# ziffy_board_v2.net
KiCad netlist of a schematic drawn in EAGLE
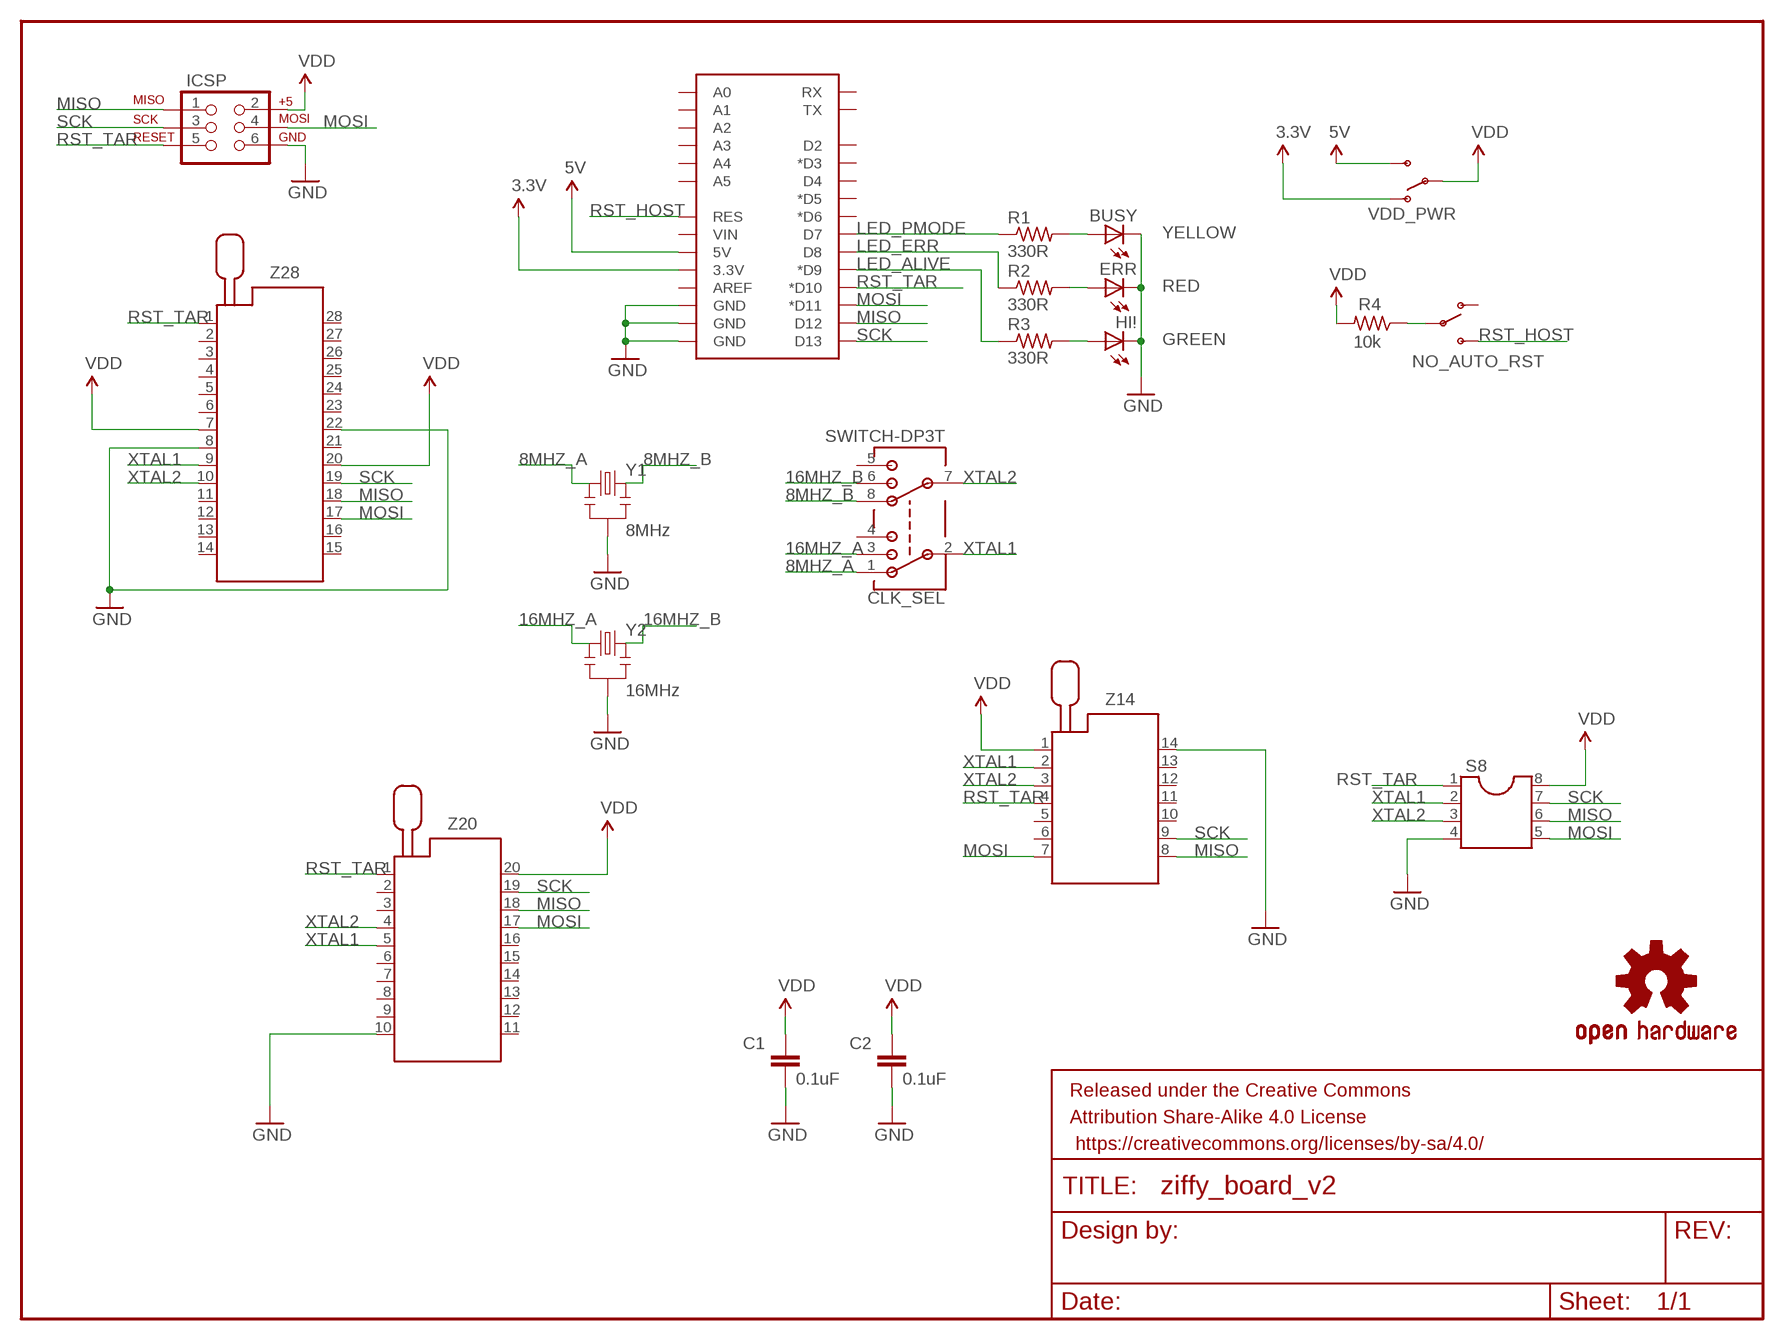
[diagram p0: schematic, sheet 1]

(export (version "E")
  (design (tool "Eeschema 10.0.6"))
  (components
    (comp (ref "BUSY")
      (value "YELLOW")
      (footprint "eagle-import:LED3MM")
      (libsource (lib "eagle-import") (part "LED3MM"))
    )
    (comp (ref "C1")
      (value "0.1uF")
      (footprint "eagle-import:C025-025X050")
      (libsource (lib "eagle-import") (part "C-EU025-025X050"))
    )
    (comp (ref "C2")
      (value "0.1uF")
      (footprint "eagle-import:C025-025X050")
      (libsource (lib "eagle-import") (part "C-EU025-025X050"))
    )
    (comp (ref "CLK_SEL")
      (value "SWITCH-DP3T")
      (footprint "eagle-import:SWITCH-DP3T")
      (libsource (lib "eagle-import") (part "SWITCH-DP3T"))
    )
    (comp (ref "ERR")
      (value "RED")
      (footprint "eagle-import:LED3MM")
      (libsource (lib "eagle-import") (part "LED3MM"))
    )
    (comp (ref "FRAME1")
      (value "FRAME-LETTER")
      (footprint "eagle-import:CREATIVE_COMMONS")
      (libsource (lib "eagle-import") (part "FRAME-LETTER"))
    )
    (comp (ref "HI!")
      (value "GREEN")
      (footprint "eagle-import:LED3MM")
      (libsource (lib "eagle-import") (part "LED3MM"))
    )
    (comp (ref "ICSP")
      (value "AVR_SPI_PRG_6PTH")
      (footprint "eagle-import:2X3")
      (libsource (lib "eagle-import") (part "AVR_SPI_PRG_6PTH"))
    )
    (comp (ref "LOGO1")
      (value "OSHW-LOGOS")
      (footprint "eagle-import:OSHW-LOGO-S")
      (libsource (lib "eagle-import") (part "OSHW-LOGOS"))
    )
    (comp (ref "NO_AUTO_RST")
      (value "SWITCH-SPDTPTH")
      (footprint "eagle-import:SWITCH-SPDT")
      (libsource (lib "eagle-import") (part "SWITCH-SPDTPTH"))
    )
    (comp (ref "R1")
      (value "330R")
      (footprint "eagle-import:0204_5")
      (libsource (lib "eagle-import") (part "R-US_0204/5"))
    )
    (comp (ref "R2")
      (value "330R")
      (footprint "eagle-import:0204_5")
      (libsource (lib "eagle-import") (part "R-US_0204/5"))
    )
    (comp (ref "R3")
      (value "330R")
      (footprint "eagle-import:0204_5")
      (libsource (lib "eagle-import") (part "R-US_0204/5"))
    )
    (comp (ref "R4")
      (value "10k")
      (footprint "eagle-import:0204_5")
      (libsource (lib "eagle-import") (part "R-US_0204/5"))
    )
    (comp (ref "S8")
      (value "DIPSHIT")
      (footprint "eagle-import:DIL08")
      (libsource (lib "eagle-import") (part "DIL8"))
    )
    (comp (ref "U$1")
      (value "ARDUINO_SHIELD")
      (footprint "eagle-import:SHIELD_NO_OUTLINE")
      (libsource (lib "eagle-import") (part "ARDUINO_SHIELD"))
    )
    (comp (ref "VDD_PWR")
      (value "SWITCH-SPDTPTH")
      (footprint "eagle-import:SWITCH-SPDT")
      (libsource (lib "eagle-import") (part "SWITCH-SPDTPTH"))
    )
    (comp (ref "Y1")
      (value "8MHz")
      (footprint "eagle-import:RESONATOR-PTH")
      (libsource (lib "eagle-import") (part "RESONATORPTH"))
    )
    (comp (ref "Y2")
      (value "16MHz")
      (footprint "eagle-import:RESONATOR-PTH")
      (libsource (lib "eagle-import") (part "RESONATORPTH"))
    )
    (comp (ref "Z14")
      (value "ZIF14")
      (footprint "eagle-import:ZIF14")
      (fields (field (name "MF") "3M") (field (name "MPN") "214-3339-00-0602J"))
      (libsource (lib "eagle-import") (part "ZIF14"))
    )
    (comp (ref "Z20")
      (value "ZIF20")
      (footprint "eagle-import:ZIF20")
      (fields (field (name "MF") "3M") (field (name "MPN") "220-3342-00-0602J"))
      (libsource (lib "eagle-import") (part "ZIF20"))
    )
    (comp (ref "Z28")
      (value "ZIF28")
      (footprint "eagle-import:ZIF28")
      (libsource (lib "eagle-import") (part "ZIF28"))
    )
  )
  (nets
    (net (code "1") (name "/8MHZ_A") (class "Default")
      (node (ref "CLK_SEL") (pin "1") (pinfunction "1_1") (pintype "bidirectional"))
      (node (ref "Y1") (pin "1") (pinfunction "1_1") (pintype "passive"))
    )
    (net (code "2") (name "/8MHZ_B") (class "Default")
      (node (ref "CLK_SEL") (pin "8") (pinfunction "8_8") (pintype "bidirectional"))
      (node (ref "Y1") (pin "3") (pinfunction "3_3") (pintype "passive"))
    )
    (net (code "3") (name "/16MHZ_A") (class "Default")
      (node (ref "CLK_SEL") (pin "3") (pinfunction "3_3") (pintype "bidirectional"))
      (node (ref "Y2") (pin "1") (pinfunction "1_1") (pintype "passive"))
    )
    (net (code "4") (name "/16MHZ_B") (class "Default")
      (node (ref "CLK_SEL") (pin "6") (pinfunction "6_6") (pintype "bidirectional"))
      (node (ref "Y2") (pin "3") (pinfunction "3_3") (pintype "passive"))
    )
    (net (code "5") (name "/LED_ALIVE") (class "Default")
      (node (ref "R3") (pin "1") (pinfunction "1_1") (pintype "passive"))
      (node (ref "U$1") (pin "D9") (pinfunction "*D9_D9") (pintype "bidirectional"))
    )
    (net (code "6") (name "/LED_ERR") (class "Default")
      (node (ref "R2") (pin "1") (pinfunction "1_1") (pintype "passive"))
      (node (ref "U$1") (pin "D8") (pinfunction "D8_D8") (pintype "bidirectional"))
    )
    (net (code "7") (name "/LED_PMODE") (class "Default")
      (node (ref "R1") (pin "1") (pinfunction "1_1") (pintype "passive"))
      (node (ref "U$1") (pin "D7") (pinfunction "D7_D7") (pintype "bidirectional"))
    )
    (net (code "8") (name "/MISO") (class "Default")
      (node (ref "ICSP") (pin "1") (pinfunction "1_1") (pintype "passive"))
      (node (ref "S8") (pin "6") (pinfunction "6_6") (pintype "passive"))
      (node (ref "U$1") (pin "D12") (pinfunction "D12_D12") (pintype "bidirectional"))
      (node (ref "Z14") (pin "8") (pinfunction "8_8") (pintype "passive"))
      (node (ref "Z20") (pin "18") (pinfunction "18_18") (pintype "passive"))
      (node (ref "Z28") (pin "18") (pinfunction "18_18") (pintype "passive"))
    )
    (net (code "9") (name "/MOSI") (class "Default")
      (node (ref "ICSP") (pin "4") (pinfunction "4_4") (pintype "passive"))
      (node (ref "S8") (pin "5") (pinfunction "5_5") (pintype "passive"))
      (node (ref "U$1") (pin "D11") (pinfunction "*D11_D11") (pintype "bidirectional"))
      (node (ref "Z14") (pin "7") (pinfunction "7_7") (pintype "passive"))
      (node (ref "Z20") (pin "17") (pinfunction "17_17") (pintype "passive"))
      (node (ref "Z28") (pin "17") (pinfunction "17_17") (pintype "passive"))
    )
    (net (code "10") (name "/RST_HOST") (class "Default")
      (node (ref "NO_AUTO_RST") (pin "3") (pinfunction "S_3") (pintype "passive"))
      (node (ref "U$1") (pin "RES") (pinfunction "RES_RES") (pintype "bidirectional"))
    )
    (net (code "11") (name "/RST_TAR") (class "Default")
      (node (ref "ICSP") (pin "5") (pinfunction "5_5") (pintype "passive"))
      (node (ref "S8") (pin "1") (pinfunction "1_1") (pintype "passive"))
      (node (ref "U$1") (pin "D10") (pinfunction "*D10_D10") (pintype "bidirectional"))
      (node (ref "Z14") (pin "4") (pinfunction "4_4") (pintype "passive"))
      (node (ref "Z20") (pin "1") (pinfunction "1_1") (pintype "passive"))
      (node (ref "Z28") (pin "1") (pinfunction "1_1") (pintype "passive"))
    )
    (net (code "12") (name "/SCK") (class "Default")
      (node (ref "ICSP") (pin "3") (pinfunction "3_3") (pintype "passive"))
      (node (ref "S8") (pin "7") (pinfunction "7_7") (pintype "passive"))
      (node (ref "U$1") (pin "D13") (pinfunction "D13_D13") (pintype "bidirectional"))
      (node (ref "Z14") (pin "9") (pinfunction "9_9") (pintype "passive"))
      (node (ref "Z20") (pin "19") (pinfunction "19_19") (pintype "passive"))
      (node (ref "Z28") (pin "19") (pinfunction "19_19") (pintype "passive"))
    )
    (net (code "13") (name "/XTAL1") (class "Default")
      (node (ref "CLK_SEL") (pin "2") (pinfunction "2_2") (pintype "bidirectional"))
      (node (ref "S8") (pin "2") (pinfunction "2_2") (pintype "passive"))
      (node (ref "Z14") (pin "2") (pinfunction "2_2") (pintype "passive"))
      (node (ref "Z20") (pin "5") (pinfunction "5_5") (pintype "passive"))
      (node (ref "Z28") (pin "9") (pinfunction "9_9") (pintype "passive"))
    )
    (net (code "14") (name "/XTAL2") (class "Default")
      (node (ref "CLK_SEL") (pin "7") (pinfunction "7_7") (pintype "bidirectional"))
      (node (ref "S8") (pin "3") (pinfunction "3_3") (pintype "passive"))
      (node (ref "Z14") (pin "3") (pinfunction "3_3") (pintype "passive"))
      (node (ref "Z20") (pin "4") (pinfunction "4_4") (pintype "passive"))
      (node (ref "Z28") (pin "10") (pinfunction "10_10") (pintype "passive"))
    )
    (net (code "15") (name "3.3V") (class "Default")
      (node (ref "U$1") (pin "3.3V") (pinfunction "3.3V_3.3V") (pintype "bidirectional"))
      (node (ref "VDD_PWR") (pin "1") (pinfunction "O_1") (pintype "passive"))
    )
    (net (code "16") (name "5V") (class "Default")
      (node (ref "U$1") (pin "5V") (pinfunction "5V_5V") (pintype "bidirectional"))
      (node (ref "VDD_PWR") (pin "3") (pinfunction "S_3") (pintype "passive"))
    )
    (net (code "17") (name "GND") (class "Default")
      (node (ref "BUSY") (pin "K") (pinfunction "C_K") (pintype "passive"))
      (node (ref "C1") (pin "2") (pinfunction "2_2") (pintype "passive"))
      (node (ref "C2") (pin "2") (pinfunction "2_2") (pintype "passive"))
      (node (ref "ERR") (pin "K") (pinfunction "C_K") (pintype "passive"))
      (node (ref "HI!") (pin "K") (pinfunction "C_K") (pintype "passive"))
      (node (ref "ICSP") (pin "6") (pinfunction "6_6") (pintype "passive"))
      (node (ref "S8") (pin "4") (pinfunction "4_4") (pintype "passive"))
      (node (ref "U$1") (pin "GND@0") (pinfunction "GND_GND@0") (pintype "bidirectional"))
      (node (ref "U$1") (pin "GND@1") (pinfunction "GND_GND@1") (pintype "bidirectional"))
      (node (ref "U$1") (pin "GND@2") (pinfunction "GND_GND@2") (pintype "bidirectional"))
      (node (ref "Y1") (pin "2") (pinfunction "2_2") (pintype "passive"))
      (node (ref "Y2") (pin "2") (pinfunction "2_2") (pintype "passive"))
      (node (ref "Z14") (pin "14") (pinfunction "14_14") (pintype "passive"))
      (node (ref "Z20") (pin "10") (pinfunction "10_10") (pintype "passive"))
      (node (ref "Z28") (pin "22") (pinfunction "22_22") (pintype "passive"))
      (node (ref "Z28") (pin "8") (pinfunction "8_8") (pintype "passive"))
    )
    (net (code "18") (name "Net-(BUSY-PadA)") (class "Default")
      (node (ref "BUSY") (pin "A") (pinfunction "A_A") (pintype "passive"))
      (node (ref "R1") (pin "2") (pinfunction "2_2") (pintype "passive"))
    )
    (net (code "19") (name "Net-(ERR-PadA)") (class "Default")
      (node (ref "ERR") (pin "A") (pinfunction "A_A") (pintype "passive"))
      (node (ref "R2") (pin "2") (pinfunction "2_2") (pintype "passive"))
    )
    (net (code "20") (name "Net-(HI!-PadA)") (class "Default")
      (node (ref "HI!") (pin "A") (pinfunction "A_A") (pintype "passive"))
      (node (ref "R3") (pin "2") (pinfunction "2_2") (pintype "passive"))
    )
    (net (code "21") (name "Net-(NO_AUTO_RST-P)") (class "Default")
      (node (ref "NO_AUTO_RST") (pin "2") (pinfunction "P_2") (pintype "passive"))
      (node (ref "R4") (pin "1") (pinfunction "1_1") (pintype "passive"))
    )
    (net (code "22") (name "VDD") (class "Default")
      (node (ref "C1") (pin "1") (pinfunction "1_1") (pintype "passive"))
      (node (ref "C2") (pin "1") (pinfunction "1_1") (pintype "passive"))
      (node (ref "ICSP") (pin "2") (pinfunction "2_2") (pintype "passive"))
      (node (ref "R4") (pin "2") (pinfunction "2_2") (pintype "passive"))
      (node (ref "S8") (pin "8") (pinfunction "8_8") (pintype "passive"))
      (node (ref "VDD_PWR") (pin "2") (pinfunction "P_2") (pintype "passive"))
      (node (ref "Z14") (pin "1") (pinfunction "1_1") (pintype "passive"))
      (node (ref "Z20") (pin "20") (pinfunction "20_20") (pintype "passive"))
      (node (ref "Z28") (pin "20") (pinfunction "20_20") (pintype "passive"))
      (node (ref "Z28") (pin "7") (pinfunction "7_7") (pintype "passive"))
    )
    (net (code "23") (name "unconnected-(CLK_SEL-Pad4)") (class "Default")
      (node (ref "CLK_SEL") (pin "4") (pinfunction "4_4") (pintype "bidirectional"))
    )
    (net (code "24") (name "unconnected-(CLK_SEL-Pad5)") (class "Default")
      (node (ref "CLK_SEL") (pin "5") (pinfunction "5_5") (pintype "bidirectional"))
    )
    (net (code "25") (name "unconnected-(NO_AUTO_RST-O-Pad1)") (class "Default")
      (node (ref "NO_AUTO_RST") (pin "1") (pinfunction "O_1") (pintype "passive"))
    )
    (net (code "26") (name "unconnected-(U$1-*D3-PadD3)") (class "Default")
      (node (ref "U$1") (pin "D3") (pinfunction "*D3_D3") (pintype "bidirectional"))
    )
    (net (code "27") (name "unconnected-(U$1-*D5-PadD5)") (class "Default")
      (node (ref "U$1") (pin "D5") (pinfunction "*D5_D5") (pintype "bidirectional"))
    )
    (net (code "28") (name "unconnected-(U$1-*D6-PadD6)") (class "Default")
      (node (ref "U$1") (pin "D6") (pinfunction "*D6_D6") (pintype "bidirectional"))
    )
    (net (code "29") (name "unconnected-(U$1-PadA0)") (class "Default")
      (node (ref "U$1") (pin "A0") (pinfunction "A0_A0") (pintype "bidirectional"))
    )
    (net (code "30") (name "unconnected-(U$1-PadA1)") (class "Default")
      (node (ref "U$1") (pin "A1") (pinfunction "A1_A1") (pintype "bidirectional"))
    )
    (net (code "31") (name "unconnected-(U$1-PadA2)") (class "Default")
      (node (ref "U$1") (pin "A2") (pinfunction "A2_A2") (pintype "bidirectional"))
    )
    (net (code "32") (name "unconnected-(U$1-PadA3)") (class "Default")
      (node (ref "U$1") (pin "A3") (pinfunction "A3_A3") (pintype "bidirectional"))
    )
    (net (code "33") (name "unconnected-(U$1-PadA4)") (class "Default")
      (node (ref "U$1") (pin "A4") (pinfunction "A4_A4") (pintype "bidirectional"))
    )
    (net (code "34") (name "unconnected-(U$1-PadA5)") (class "Default")
      (node (ref "U$1") (pin "A5") (pinfunction "A5_A5") (pintype "bidirectional"))
    )
    (net (code "35") (name "unconnected-(U$1-PadAREF)") (class "Default")
      (node (ref "U$1") (pin "AREF") (pinfunction "AREF_AREF") (pintype "bidirectional"))
    )
    (net (code "36") (name "unconnected-(U$1-PadD2)") (class "Default")
      (node (ref "U$1") (pin "D2") (pinfunction "D2_D2") (pintype "bidirectional"))
    )
    (net (code "37") (name "unconnected-(U$1-PadD4)") (class "Default")
      (node (ref "U$1") (pin "D4") (pinfunction "D4_D4") (pintype "bidirectional"))
    )
    (net (code "38") (name "unconnected-(U$1-PadRX)") (class "Default")
      (node (ref "U$1") (pin "RX") (pinfunction "RX_RX") (pintype "bidirectional"))
    )
    (net (code "39") (name "unconnected-(U$1-PadTX)") (class "Default")
      (node (ref "U$1") (pin "TX") (pinfunction "TX_TX") (pintype "bidirectional"))
    )
    (net (code "40") (name "unconnected-(U$1-PadVIN)") (class "Default")
      (node (ref "U$1") (pin "VIN") (pinfunction "VIN_VIN") (pintype "bidirectional"))
    )
    (net (code "41") (name "unconnected-(Z14-Pad5)") (class "Default")
      (node (ref "Z14") (pin "5") (pinfunction "5_5") (pintype "passive"))
    )
    (net (code "42") (name "unconnected-(Z14-Pad6)") (class "Default")
      (node (ref "Z14") (pin "6") (pinfunction "6_6") (pintype "passive"))
    )
    (net (code "43") (name "unconnected-(Z14-Pad10)") (class "Default")
      (node (ref "Z14") (pin "10") (pinfunction "10_10") (pintype "passive"))
    )
    (net (code "44") (name "unconnected-(Z14-Pad11)") (class "Default")
      (node (ref "Z14") (pin "11") (pinfunction "11_11") (pintype "passive"))
    )
    (net (code "45") (name "unconnected-(Z14-Pad12)") (class "Default")
      (node (ref "Z14") (pin "12") (pinfunction "12_12") (pintype "passive"))
    )
    (net (code "46") (name "unconnected-(Z14-Pad13)") (class "Default")
      (node (ref "Z14") (pin "13") (pinfunction "13_13") (pintype "passive"))
    )
    (net (code "47") (name "unconnected-(Z20-Pad2)") (class "Default")
      (node (ref "Z20") (pin "2") (pinfunction "2_2") (pintype "passive"))
    )
    (net (code "48") (name "unconnected-(Z20-Pad3)") (class "Default")
      (node (ref "Z20") (pin "3") (pinfunction "3_3") (pintype "passive"))
    )
    (net (code "49") (name "unconnected-(Z20-Pad6)") (class "Default")
      (node (ref "Z20") (pin "6") (pinfunction "6_6") (pintype "passive"))
    )
    (net (code "50") (name "unconnected-(Z20-Pad7)") (class "Default")
      (node (ref "Z20") (pin "7") (pinfunction "7_7") (pintype "passive"))
    )
    (net (code "51") (name "unconnected-(Z20-Pad8)") (class "Default")
      (node (ref "Z20") (pin "8") (pinfunction "8_8") (pintype "passive"))
    )
    (net (code "52") (name "unconnected-(Z20-Pad9)") (class "Default")
      (node (ref "Z20") (pin "9") (pinfunction "9_9") (pintype "passive"))
    )
    (net (code "53") (name "unconnected-(Z20-Pad11)") (class "Default")
      (node (ref "Z20") (pin "11") (pinfunction "11_11") (pintype "passive"))
    )
    (net (code "54") (name "unconnected-(Z20-Pad12)") (class "Default")
      (node (ref "Z20") (pin "12") (pinfunction "12_12") (pintype "passive"))
    )
    (net (code "55") (name "unconnected-(Z20-Pad13)") (class "Default")
      (node (ref "Z20") (pin "13") (pinfunction "13_13") (pintype "passive"))
    )
    (net (code "56") (name "unconnected-(Z20-Pad14)") (class "Default")
      (node (ref "Z20") (pin "14") (pinfunction "14_14") (pintype "passive"))
    )
    (net (code "57") (name "unconnected-(Z20-Pad15)") (class "Default")
      (node (ref "Z20") (pin "15") (pinfunction "15_15") (pintype "passive"))
    )
    (net (code "58") (name "unconnected-(Z20-Pad16)") (class "Default")
      (node (ref "Z20") (pin "16") (pinfunction "16_16") (pintype "passive"))
    )
    (net (code "59") (name "unconnected-(Z28-Pad2)") (class "Default")
      (node (ref "Z28") (pin "2") (pinfunction "2_2") (pintype "passive"))
    )
    (net (code "60") (name "unconnected-(Z28-Pad3)") (class "Default")
      (node (ref "Z28") (pin "3") (pinfunction "3_3") (pintype "passive"))
    )
    (net (code "61") (name "unconnected-(Z28-Pad4)") (class "Default")
      (node (ref "Z28") (pin "4") (pinfunction "4_4") (pintype "passive"))
    )
    (net (code "62") (name "unconnected-(Z28-Pad5)") (class "Default")
      (node (ref "Z28") (pin "5") (pinfunction "5_5") (pintype "passive"))
    )
    (net (code "63") (name "unconnected-(Z28-Pad6)") (class "Default")
      (node (ref "Z28") (pin "6") (pinfunction "6_6") (pintype "passive"))
    )
    (net (code "64") (name "unconnected-(Z28-Pad11)") (class "Default")
      (node (ref "Z28") (pin "11") (pinfunction "11_11") (pintype "passive"))
    )
    (net (code "65") (name "unconnected-(Z28-Pad12)") (class "Default")
      (node (ref "Z28") (pin "12") (pinfunction "12_12") (pintype "passive"))
    )
    (net (code "66") (name "unconnected-(Z28-Pad13)") (class "Default")
      (node (ref "Z28") (pin "13") (pinfunction "13_13") (pintype "passive"))
    )
    (net (code "67") (name "unconnected-(Z28-Pad14)") (class "Default")
      (node (ref "Z28") (pin "14") (pinfunction "14_14") (pintype "passive"))
    )
    (net (code "68") (name "unconnected-(Z28-Pad15)") (class "Default")
      (node (ref "Z28") (pin "15") (pinfunction "15_15") (pintype "passive"))
    )
    (net (code "69") (name "unconnected-(Z28-Pad16)") (class "Default")
      (node (ref "Z28") (pin "16") (pinfunction "16_16") (pintype "passive"))
    )
    (net (code "70") (name "unconnected-(Z28-Pad21)") (class "Default")
      (node (ref "Z28") (pin "21") (pinfunction "21_21") (pintype "passive"))
    )
    (net (code "71") (name "unconnected-(Z28-Pad23)") (class "Default")
      (node (ref "Z28") (pin "23") (pinfunction "23_23") (pintype "passive"))
    )
    (net (code "72") (name "unconnected-(Z28-Pad24)") (class "Default")
      (node (ref "Z28") (pin "24") (pinfunction "24_24") (pintype "passive"))
    )
    (net (code "73") (name "unconnected-(Z28-Pad25)") (class "Default")
      (node (ref "Z28") (pin "25") (pinfunction "25_25") (pintype "passive"))
    )
    (net (code "74") (name "unconnected-(Z28-Pad26)") (class "Default")
      (node (ref "Z28") (pin "26") (pinfunction "26_26") (pintype "passive"))
    )
    (net (code "75") (name "unconnected-(Z28-Pad27)") (class "Default")
      (node (ref "Z28") (pin "27") (pinfunction "27_27") (pintype "passive"))
    )
    (net (code "76") (name "unconnected-(Z28-Pad28)") (class "Default")
      (node (ref "Z28") (pin "28") (pinfunction "28_28") (pintype "passive"))
    )
  )
)
